# IR_Remote_Rev_C.net
KiCad netlist of a schematic drawn in EAGLE
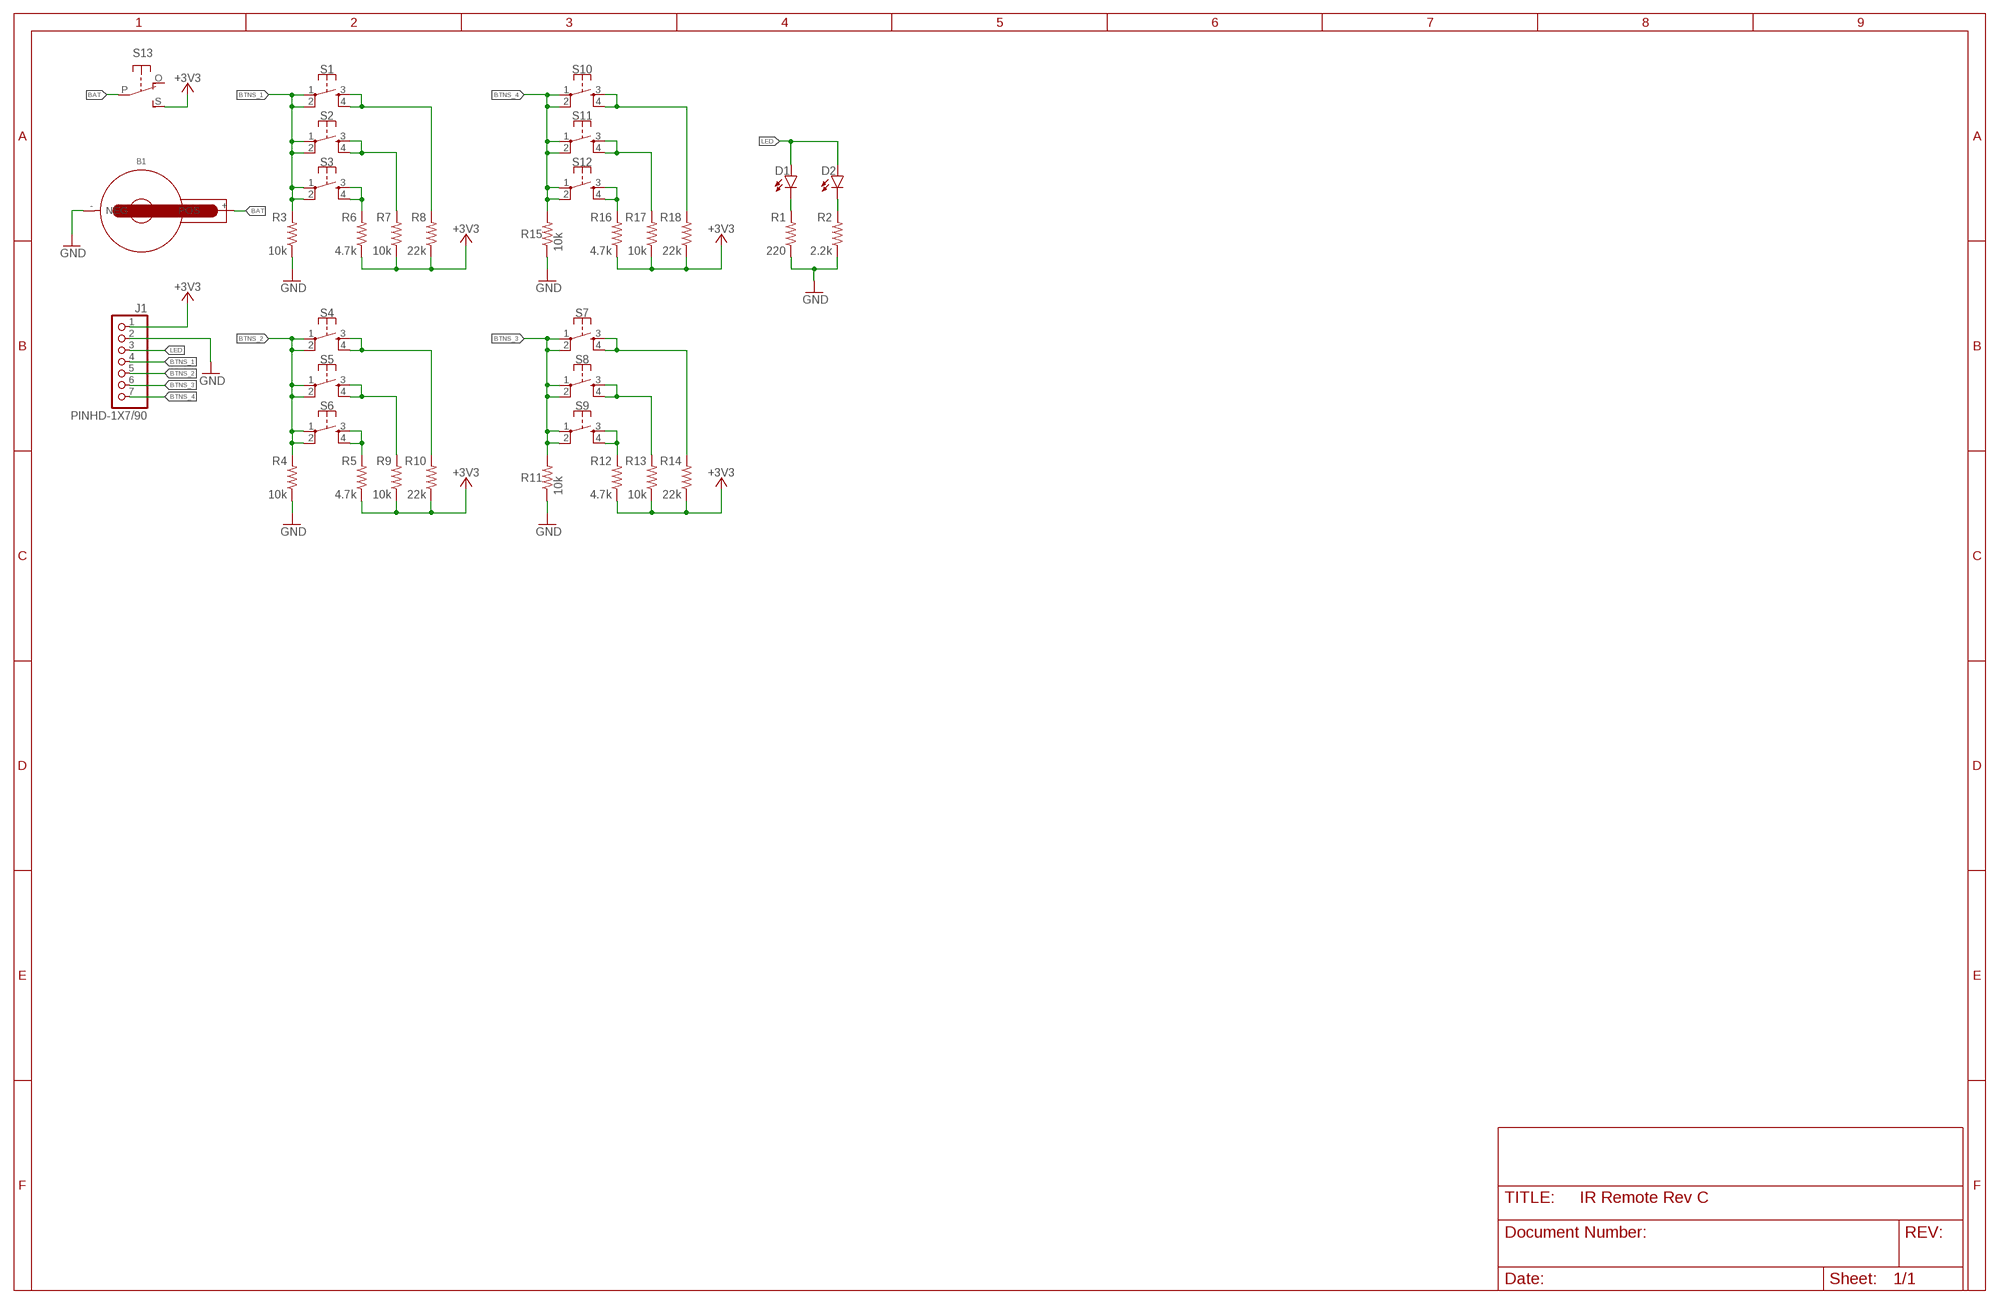
[diagram p0: schematic, sheet 1]

(export (version "E")
  (design (tool "Eeschema 10.0.6"))
  (components
    (comp (ref "B1")
      (value "WA-BCPH_79578211")
      (footprint "eagle-import:WA-BCPH_79578211")
      (libsource (lib "eagle-import") (part "WA-BCPH_79578211"))
    )
    (comp (ref "D1")
      (value "LED90")
      (footprint "eagle-import:LED5MM-90")
      (libsource (lib "eagle-import") (part "LED90"))
    )
    (comp (ref "D2")
      (value "LED90")
      (footprint "eagle-import:LED5MM-90")
      (libsource (lib "eagle-import") (part "LED90"))
    )
    (comp (ref "J1")
      (value "PINHD-1X7/90")
      (footprint "eagle-import:1X07_90")
      (libsource (lib "eagle-import") (part "PINHD-1X7/90"))
    )
    (comp (ref "R1")
      (value "220")
      (footprint "eagle-import:0207_10")
      (libsource (lib "eagle-import") (part "RESISTOR"))
    )
    (comp (ref "R2")
      (value "2.2k")
      (footprint "eagle-import:0207_10")
      (libsource (lib "eagle-import") (part "RESISTOR"))
    )
    (comp (ref "R3")
      (value "10k")
      (footprint "eagle-import:0207_10")
      (libsource (lib "eagle-import") (part "RESISTOR"))
    )
    (comp (ref "R4")
      (value "10k")
      (footprint "eagle-import:0207_10")
      (libsource (lib "eagle-import") (part "RESISTOR"))
    )
    (comp (ref "R5")
      (value "4.7k")
      (footprint "eagle-import:0207_10")
      (libsource (lib "eagle-import") (part "RESISTOR"))
    )
    (comp (ref "R6")
      (value "4.7k")
      (footprint "eagle-import:0207_10")
      (libsource (lib "eagle-import") (part "RESISTOR"))
    )
    (comp (ref "R7")
      (value "10k")
      (footprint "eagle-import:0207_10")
      (libsource (lib "eagle-import") (part "RESISTOR"))
    )
    (comp (ref "R8")
      (value "22k")
      (footprint "eagle-import:0207_10")
      (libsource (lib "eagle-import") (part "RESISTOR"))
    )
    (comp (ref "R9")
      (value "10k")
      (footprint "eagle-import:0207_10")
      (libsource (lib "eagle-import") (part "RESISTOR"))
    )
    (comp (ref "R10")
      (value "22k")
      (footprint "eagle-import:0207_10")
      (libsource (lib "eagle-import") (part "RESISTOR"))
    )
    (comp (ref "R11")
      (value "10k")
      (footprint "eagle-import:0207_10")
      (libsource (lib "eagle-import") (part "RESISTOR"))
    )
    (comp (ref "R12")
      (value "4.7k")
      (footprint "eagle-import:0207_10")
      (libsource (lib "eagle-import") (part "RESISTOR"))
    )
    (comp (ref "R13")
      (value "10k")
      (footprint "eagle-import:0207_10")
      (libsource (lib "eagle-import") (part "RESISTOR"))
    )
    (comp (ref "R14")
      (value "22k")
      (footprint "eagle-import:0207_10")
      (libsource (lib "eagle-import") (part "RESISTOR"))
    )
    (comp (ref "R15")
      (value "10k")
      (footprint "eagle-import:0207_10")
      (libsource (lib "eagle-import") (part "RESISTOR"))
    )
    (comp (ref "R16")
      (value "4.7k")
      (footprint "eagle-import:0207_10")
      (libsource (lib "eagle-import") (part "RESISTOR"))
    )
    (comp (ref "R17")
      (value "10k")
      (footprint "eagle-import:0207_10")
      (libsource (lib "eagle-import") (part "RESISTOR"))
    )
    (comp (ref "R18")
      (value "22k")
      (footprint "eagle-import:0207_10")
      (libsource (lib "eagle-import") (part "RESISTOR"))
    )
    (comp (ref "S1")
      (value "TACTILE-BUTTON40XX")
      (footprint "eagle-import:B3F-40XX")
      (libsource (lib "eagle-import") (part "TACTILE-BUTTON40XX"))
    )
    (comp (ref "S2")
      (value "TACTILE-BUTTON40XX")
      (footprint "eagle-import:B3F-40XX")
      (libsource (lib "eagle-import") (part "TACTILE-BUTTON40XX"))
    )
    (comp (ref "S3")
      (value "TACTILE-BUTTON40XX")
      (footprint "eagle-import:B3F-40XX")
      (libsource (lib "eagle-import") (part "TACTILE-BUTTON40XX"))
    )
    (comp (ref "S4")
      (value "TACTILE-BUTTON40XX")
      (footprint "eagle-import:B3F-40XX")
      (libsource (lib "eagle-import") (part "TACTILE-BUTTON40XX"))
    )
    (comp (ref "S5")
      (value "TACTILE-BUTTON40XX")
      (footprint "eagle-import:B3F-40XX")
      (libsource (lib "eagle-import") (part "TACTILE-BUTTON40XX"))
    )
    (comp (ref "S6")
      (value "TACTILE-BUTTON40XX")
      (footprint "eagle-import:B3F-40XX")
      (libsource (lib "eagle-import") (part "TACTILE-BUTTON40XX"))
    )
    (comp (ref "S7")
      (value "TACTILE-BUTTON40XX")
      (footprint "eagle-import:B3F-40XX")
      (libsource (lib "eagle-import") (part "TACTILE-BUTTON40XX"))
    )
    (comp (ref "S8")
      (value "TACTILE-BUTTON40XX")
      (footprint "eagle-import:B3F-40XX")
      (libsource (lib "eagle-import") (part "TACTILE-BUTTON40XX"))
    )
    (comp (ref "S9")
      (value "TACTILE-BUTTON40XX")
      (footprint "eagle-import:B3F-40XX")
      (libsource (lib "eagle-import") (part "TACTILE-BUTTON40XX"))
    )
    (comp (ref "S10")
      (value "TACTILE-BUTTON40XX")
      (footprint "eagle-import:B3F-40XX")
      (libsource (lib "eagle-import") (part "TACTILE-BUTTON40XX"))
    )
    (comp (ref "S11")
      (value "TACTILE-BUTTON40XX")
      (footprint "eagle-import:B3F-40XX")
      (libsource (lib "eagle-import") (part "TACTILE-BUTTON40XX"))
    )
    (comp (ref "S12")
      (value "TACTILE-BUTTON40XX")
      (footprint "eagle-import:B3F-40XX")
      (libsource (lib "eagle-import") (part "TACTILE-BUTTON40XX"))
    )
    (comp (ref "S13")
      (value "SLIDE-SWITCHSIDE")
      (footprint "eagle-import:EG1270-90")
      (libsource (lib "eagle-import") (part "SLIDE-SWITCHSIDE"))
    )
  )
  (nets
    (net (code "1") (name "+3V3") (class "Default")
      (node (ref "J1") (pin "1") (pinfunction "1_1") (pintype "passive"))
      (node (ref "R10") (pin "1") (pinfunction "1_1") (pintype "passive"))
      (node (ref "R12") (pin "1") (pinfunction "1_1") (pintype "passive"))
      (node (ref "R13") (pin "1") (pinfunction "1_1") (pintype "passive"))
      (node (ref "R14") (pin "1") (pinfunction "1_1") (pintype "passive"))
      (node (ref "R16") (pin "1") (pinfunction "1_1") (pintype "passive"))
      (node (ref "R17") (pin "1") (pinfunction "1_1") (pintype "passive"))
      (node (ref "R18") (pin "1") (pinfunction "1_1") (pintype "passive"))
      (node (ref "R5") (pin "1") (pinfunction "1_1") (pintype "passive"))
      (node (ref "R6") (pin "1") (pinfunction "1_1") (pintype "passive"))
      (node (ref "R7") (pin "1") (pinfunction "1_1") (pintype "passive"))
      (node (ref "R8") (pin "1") (pinfunction "1_1") (pintype "passive"))
      (node (ref "R9") (pin "1") (pinfunction "1_1") (pintype "passive"))
      (node (ref "S13") (pin "S") (pinfunction "S_S") (pintype "passive"))
    )
    (net (code "2") (name "BAT") (class "Default")
      (node (ref "B1") (pin "+") (pinfunction "POS_+") (pintype "passive"))
      (node (ref "S13") (pin "P") (pinfunction "P_P") (pintype "passive"))
    )
    (net (code "3") (name "BTNS_1") (class "Default")
      (node (ref "J1") (pin "4") (pinfunction "4_4") (pintype "passive"))
      (node (ref "R3") (pin "2") (pinfunction "2_2") (pintype "passive"))
      (node (ref "S1") (pin "1") (pinfunction "P_1") (pintype "passive"))
      (node (ref "S1") (pin "2") (pinfunction "P1_2") (pintype "passive"))
      (node (ref "S2") (pin "1") (pinfunction "P_1") (pintype "passive"))
      (node (ref "S2") (pin "2") (pinfunction "P1_2") (pintype "passive"))
      (node (ref "S3") (pin "1") (pinfunction "P_1") (pintype "passive"))
      (node (ref "S3") (pin "2") (pinfunction "P1_2") (pintype "passive"))
    )
    (net (code "4") (name "BTNS_2") (class "Default")
      (node (ref "J1") (pin "5") (pinfunction "5_5") (pintype "passive"))
      (node (ref "R4") (pin "2") (pinfunction "2_2") (pintype "passive"))
      (node (ref "S4") (pin "1") (pinfunction "P_1") (pintype "passive"))
      (node (ref "S4") (pin "2") (pinfunction "P1_2") (pintype "passive"))
      (node (ref "S5") (pin "1") (pinfunction "P_1") (pintype "passive"))
      (node (ref "S5") (pin "2") (pinfunction "P1_2") (pintype "passive"))
      (node (ref "S6") (pin "1") (pinfunction "P_1") (pintype "passive"))
      (node (ref "S6") (pin "2") (pinfunction "P1_2") (pintype "passive"))
    )
    (net (code "5") (name "BTNS_3") (class "Default")
      (node (ref "J1") (pin "6") (pinfunction "6_6") (pintype "passive"))
      (node (ref "R11") (pin "2") (pinfunction "2_2") (pintype "passive"))
      (node (ref "S7") (pin "1") (pinfunction "P_1") (pintype "passive"))
      (node (ref "S7") (pin "2") (pinfunction "P1_2") (pintype "passive"))
      (node (ref "S8") (pin "1") (pinfunction "P_1") (pintype "passive"))
      (node (ref "S8") (pin "2") (pinfunction "P1_2") (pintype "passive"))
      (node (ref "S9") (pin "1") (pinfunction "P_1") (pintype "passive"))
      (node (ref "S9") (pin "2") (pinfunction "P1_2") (pintype "passive"))
    )
    (net (code "6") (name "BTNS_4") (class "Default")
      (node (ref "J1") (pin "7") (pinfunction "7_7") (pintype "passive"))
      (node (ref "R15") (pin "2") (pinfunction "2_2") (pintype "passive"))
      (node (ref "S10") (pin "1") (pinfunction "P_1") (pintype "passive"))
      (node (ref "S10") (pin "2") (pinfunction "P1_2") (pintype "passive"))
      (node (ref "S11") (pin "1") (pinfunction "P_1") (pintype "passive"))
      (node (ref "S11") (pin "2") (pinfunction "P1_2") (pintype "passive"))
      (node (ref "S12") (pin "1") (pinfunction "P_1") (pintype "passive"))
      (node (ref "S12") (pin "2") (pinfunction "P1_2") (pintype "passive"))
    )
    (net (code "7") (name "GND") (class "Default")
      (node (ref "B1") (pin "-") (pinfunction "NEG_-") (pintype "passive"))
      (node (ref "J1") (pin "2") (pinfunction "2_2") (pintype "passive"))
      (node (ref "R1") (pin "1") (pinfunction "1_1") (pintype "passive"))
      (node (ref "R11") (pin "1") (pinfunction "1_1") (pintype "passive"))
      (node (ref "R15") (pin "1") (pinfunction "1_1") (pintype "passive"))
      (node (ref "R2") (pin "1") (pinfunction "1_1") (pintype "passive"))
      (node (ref "R3") (pin "1") (pinfunction "1_1") (pintype "passive"))
      (node (ref "R4") (pin "1") (pinfunction "1_1") (pintype "passive"))
    )
    (net (code "8") (name "LED") (class "Default")
      (node (ref "D1") (pin "A") (pinfunction "A_A") (pintype "passive"))
      (node (ref "D2") (pin "A") (pinfunction "A_A") (pintype "passive"))
      (node (ref "J1") (pin "3") (pinfunction "3_3") (pintype "passive"))
    )
    (net (code "9") (name "Net-(D1-C)") (class "Default")
      (node (ref "D1") (pin "K") (pinfunction "C_K") (pintype "passive"))
      (node (ref "R1") (pin "2") (pinfunction "2_2") (pintype "passive"))
    )
    (net (code "10") (name "Net-(D2-C)") (class "Default")
      (node (ref "D2") (pin "K") (pinfunction "C_K") (pintype "passive"))
      (node (ref "R2") (pin "2") (pinfunction "2_2") (pintype "passive"))
    )
    (net (code "11") (name "Net-(S1-S)") (class "Default")
      (node (ref "R8") (pin "2") (pinfunction "2_2") (pintype "passive"))
      (node (ref "S1") (pin "3") (pinfunction "S_3") (pintype "passive"))
      (node (ref "S1") (pin "4") (pinfunction "S1_4") (pintype "passive"))
    )
    (net (code "12") (name "Net-(S2-S)") (class "Default")
      (node (ref "R7") (pin "2") (pinfunction "2_2") (pintype "passive"))
      (node (ref "S2") (pin "3") (pinfunction "S_3") (pintype "passive"))
      (node (ref "S2") (pin "4") (pinfunction "S1_4") (pintype "passive"))
    )
    (net (code "13") (name "Net-(S3-S)") (class "Default")
      (node (ref "R6") (pin "2") (pinfunction "2_2") (pintype "passive"))
      (node (ref "S3") (pin "3") (pinfunction "S_3") (pintype "passive"))
      (node (ref "S3") (pin "4") (pinfunction "S1_4") (pintype "passive"))
    )
    (net (code "14") (name "Net-(S4-S)") (class "Default")
      (node (ref "R10") (pin "2") (pinfunction "2_2") (pintype "passive"))
      (node (ref "S4") (pin "3") (pinfunction "S_3") (pintype "passive"))
      (node (ref "S4") (pin "4") (pinfunction "S1_4") (pintype "passive"))
    )
    (net (code "15") (name "Net-(S5-S)") (class "Default")
      (node (ref "R9") (pin "2") (pinfunction "2_2") (pintype "passive"))
      (node (ref "S5") (pin "3") (pinfunction "S_3") (pintype "passive"))
      (node (ref "S5") (pin "4") (pinfunction "S1_4") (pintype "passive"))
    )
    (net (code "16") (name "Net-(S6-S)") (class "Default")
      (node (ref "R5") (pin "2") (pinfunction "2_2") (pintype "passive"))
      (node (ref "S6") (pin "3") (pinfunction "S_3") (pintype "passive"))
      (node (ref "S6") (pin "4") (pinfunction "S1_4") (pintype "passive"))
    )
    (net (code "17") (name "Net-(S7-S)") (class "Default")
      (node (ref "R14") (pin "2") (pinfunction "2_2") (pintype "passive"))
      (node (ref "S7") (pin "3") (pinfunction "S_3") (pintype "passive"))
      (node (ref "S7") (pin "4") (pinfunction "S1_4") (pintype "passive"))
    )
    (net (code "18") (name "Net-(S8-S)") (class "Default")
      (node (ref "R13") (pin "2") (pinfunction "2_2") (pintype "passive"))
      (node (ref "S8") (pin "3") (pinfunction "S_3") (pintype "passive"))
      (node (ref "S8") (pin "4") (pinfunction "S1_4") (pintype "passive"))
    )
    (net (code "19") (name "Net-(S9-S)") (class "Default")
      (node (ref "R12") (pin "2") (pinfunction "2_2") (pintype "passive"))
      (node (ref "S9") (pin "3") (pinfunction "S_3") (pintype "passive"))
      (node (ref "S9") (pin "4") (pinfunction "S1_4") (pintype "passive"))
    )
    (net (code "20") (name "Net-(S10-S)") (class "Default")
      (node (ref "R18") (pin "2") (pinfunction "2_2") (pintype "passive"))
      (node (ref "S10") (pin "3") (pinfunction "S_3") (pintype "passive"))
      (node (ref "S10") (pin "4") (pinfunction "S1_4") (pintype "passive"))
    )
    (net (code "21") (name "Net-(S11-S)") (class "Default")
      (node (ref "R17") (pin "2") (pinfunction "2_2") (pintype "passive"))
      (node (ref "S11") (pin "3") (pinfunction "S_3") (pintype "passive"))
      (node (ref "S11") (pin "4") (pinfunction "S1_4") (pintype "passive"))
    )
    (net (code "22") (name "Net-(S12-S)") (class "Default")
      (node (ref "R16") (pin "2") (pinfunction "2_2") (pintype "passive"))
      (node (ref "S12") (pin "3") (pinfunction "S_3") (pintype "passive"))
      (node (ref "S12") (pin "4") (pinfunction "S1_4") (pintype "passive"))
    )
    (net (code "23") (name "unconnected-(S13-PadO)") (class "Default")
      (node (ref "S13") (pin "O") (pinfunction "O_O") (pintype "passive"))
    )
  )
)
